# Sheet2.net
KiCad netlist of a schematic drawn in Altium Designer
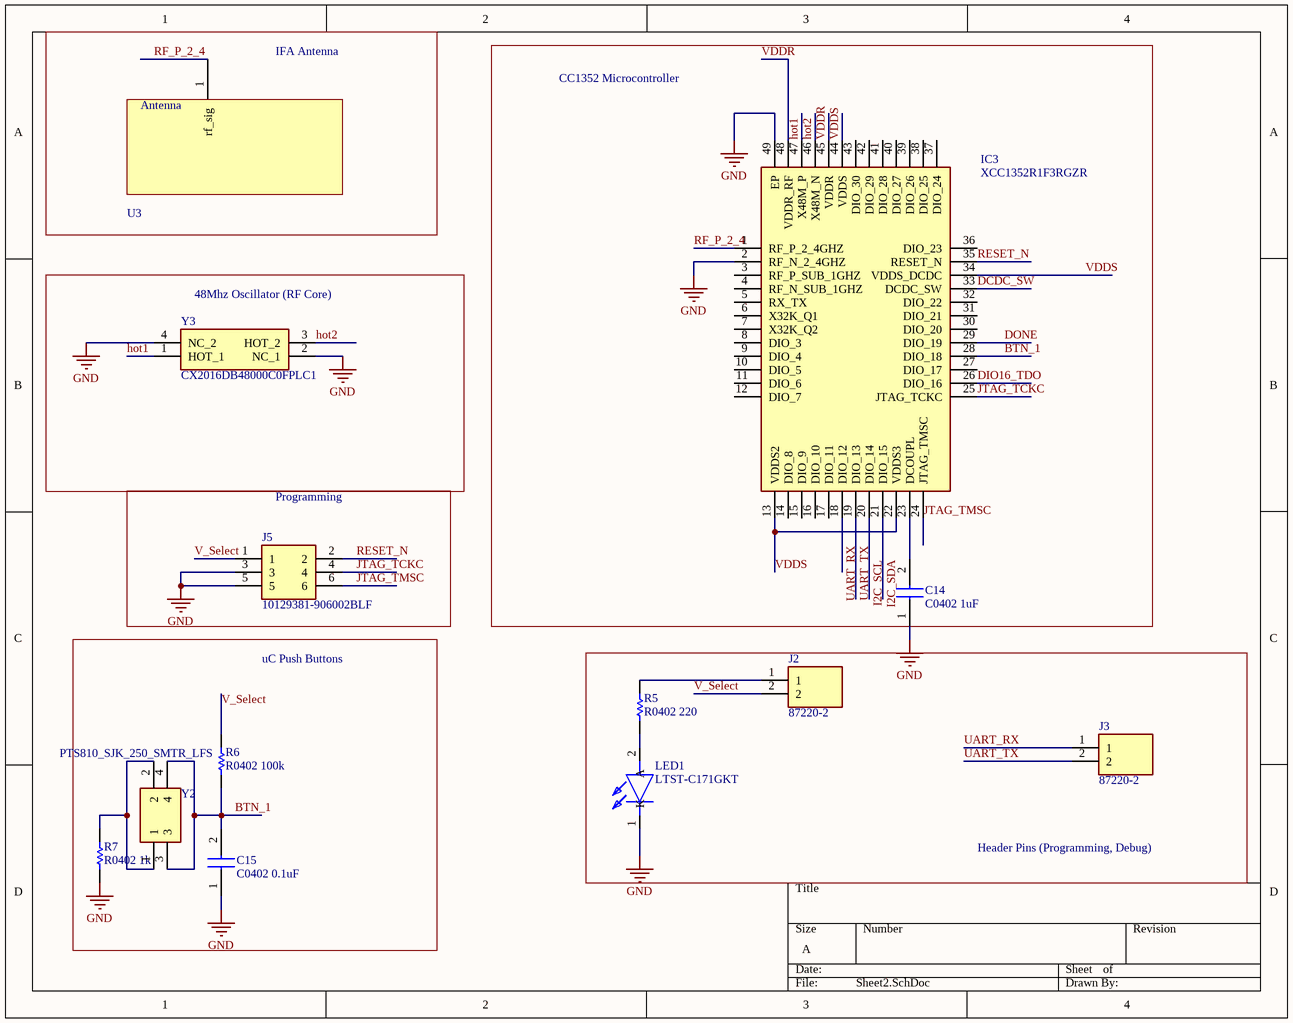
[diagram p0: Sheet2.SchDoc]

(export (version "E")
  (design (tool "Eeschema 10.0.6"))
  (components
    (comp (ref "C14")
      (value "C0402 1uF")
      (footprint "SamacSys:CAPC0603X33N")
      (description "Capacitor")
      (fields
        (field (name "MANUFACTURER_PART_NUMBER") "02014D474MAT2A")
        (field (name "MOUSER PART NUMBER") "581-02014D474MAT2A")
      )
      (libsource (lib "*") (part "02014D474MAT2A"))
    )
    (comp (ref "C15")
      (value "C0402 0.1uF")
      (footprint "SamacSys:CAPC0603X33N")
      (description "Capacitor")
      (fields
        (field (name "MANUFACTURER_PART_NUMBER") "02014D474MAT2A")
        (field (name "MOUSER PART NUMBER") "581-02014D474MAT2A")
      )
      (libsource (lib "*") (part "02014D474MAT2A"))
    )
    (comp (ref "IC3")
      (value "XCC1352R1F3RGZR")
      (footprint "SamacSys:QFN50P700X700X100-49N-D")
      (description "Integrated Circuit")
      (libsource (lib "*") (part "XCC1352R1F3RGZR"))
    )
    (comp (ref "J2")
      (value "87220-2")
      (footprint "SamacSys:HDRV2W67P0X254_1X2_467X234X1083P")
      (description "Connector")
      (fields (field (name "MOUSER PART NUMBER") "571-872202") (field (name "RS PART NUMBER") "7202418P"))
      (libsource (lib "*") (part "87220-2"))
    )
    (comp (ref "J3")
      (value "87220-2")
      (footprint "SamacSys:HDRV2W67P0X254_1X2_467X234X1083P")
      (description "Connector")
      (fields (field (name "MOUSER PART NUMBER") "571-872202") (field (name "RS PART NUMBER") "7202418P"))
      (libsource (lib "*") (part "87220-2"))
    )
    (comp (ref "J5")
      (value "10129381-906002BLF")
      (footprint "SamacSys:HDRV6W67P254_2X3_762X483X858P")
      (description "Connector")
      (fields (field (name "MOUSER PART NUMBER") "649-1012938190602BLF"))
      (libsource (lib "*") (part "10129381-906002BLF"))
    )
    (comp (ref "LED1")
      (value "LTST-C171GKT")
      (footprint "SamacSys:LEDC2012X90N")
      (description "LED")
      (fields
        (field (name "MOUSER PART NUMBER") "859-LTST-C171GKT")
        (field (name "RS PART NUMBER") "6920935P")
      )
      (libsource (lib "*") (part "LTST-C171GKT"))
    )
    (comp (ref "R5")
      (value "R0402 220")
      (footprint "RESC1005X40X25NL05T05")
      (fields (field (name "MANUFACTURER") "Vishay Dale") (field (name "PART NUMBER") "CRCW040210K0FKED"))
      (libsource (lib "Altium Content Vault") (part "RES"))
    )
    (comp (ref "R6")
      (value "R0402 100k")
      (footprint "RESC1005X40X25NL05T05")
      (fields (field (name "MANUFACTURER") "Vishay Dale") (field (name "PART NUMBER") "CRCW040210K0FKED"))
      (libsource (lib "Altium Content Vault") (part "RES"))
    )
    (comp (ref "R7")
      (value "R0402 1k")
      (footprint "RESC1005X40X25NL05T05")
      (fields (field (name "MANUFACTURER") "Vishay Dale") (field (name "PART NUMBER") "CRCW040210K0FKED"))
      (libsource (lib "Altium Content Vault") (part "RES"))
    )
    (comp (ref "U3")
      (value "RF_ANTENNA_2")
      (footprint "RF_TRACE_ANTENNA_2")
      (libsource (lib "V3_Lib") (part "RF_ANTENNA_2"))
    )
    (comp (ref "Y2")
      (value "PTS810_SJK_250_SMTR_LFS")
      (footprint "SamacSys:PTS810SJK250SMTRLFS")
      (description "Crystal or Oscillator")
      (fields
        (field (name "MANUFACTURER_PART_NUMBER") "PTS810 SJK 250 SMTR LFS")
        (field (name "MOUSER PART NUMBER") "611-PTS810SJK250SMTR")
      )
      (libsource (lib "*") (part "PTS810_SJK_250_SMTR_LFS"))
    )
    (comp (ref "Y3")
      (value "CX2016DB48000C0FPLC1")
      (footprint "SamacSys:CX2016DB48000C0FPLC1")
      (description "Crystal or Oscillator")
      (fields (field (name "MOUSER PART NUMBER") "581-CX2016DB48CFPLC1"))
      (libsource (lib "*") (part "CX2016DB48000C0FPLC1"))
    )
  )
  (nets
    (net (code "1") (name "/BTN_1") (class "Default")
      (node (ref "C15") (pin "2") (pinfunction "2_2") (pintype "passive"))
      (node (ref "IC3") (pin "28") (pinfunction "DIO_18_28") (pintype "passive"))
      (node (ref "R6") (pin "1") (pinfunction "1_1") (pintype "passive"))
      (node (ref "Y2") (pin "3") (pinfunction "3_3") (pintype "passive"))
      (node (ref "Y2") (pin "4") (pinfunction "4_4") (pintype "passive"))
    )
    (net (code "2") (name "/DCDC_SW") (class "Default")
      (node (ref "IC3") (pin "33") (pinfunction "DCDC_SW_33") (pintype "passive"))
    )
    (net (code "3") (name "/DIO16_TDO") (class "Default")
      (node (ref "IC3") (pin "26") (pinfunction "DIO_16_26") (pintype "passive"))
    )
    (net (code "4") (name "/DONE") (class "Default")
      (node (ref "IC3") (pin "29") (pinfunction "DIO_19_29") (pintype "passive"))
    )
    (net (code "5") (name "/I2C_SCL") (class "Default")
      (node (ref "IC3") (pin "20") (pinfunction "DIO_14_20") (pintype "passive"))
    )
    (net (code "6") (name "/I2C_SDA") (class "Default")
      (node (ref "IC3") (pin "21") (pinfunction "DIO_15_21") (pintype "passive"))
    )
    (net (code "7") (name "/JTAG_TCKC") (class "Default")
      (node (ref "IC3") (pin "25") (pinfunction "JTAG_TCKC_25") (pintype "passive"))
      (node (ref "J5") (pin "4") (pinfunction "4_4") (pintype "passive"))
    )
    (net (code "8") (name "/JTAG_TMSC") (class "Default")
      (node (ref "IC3") (pin "24") (pinfunction "JTAG_TMSC_24") (pintype "passive"))
      (node (ref "J5") (pin "6") (pinfunction "6_6") (pintype "passive"))
    )
    (net (code "9") (name "/RESET_N") (class "Default")
      (node (ref "IC3") (pin "35") (pinfunction "RESET_N_35") (pintype "passive"))
      (node (ref "J5") (pin "2") (pinfunction "2_2") (pintype "passive"))
    )
    (net (code "10") (name "/RF_P_2_4") (class "Default")
      (node (ref "IC3") (pin "1") (pinfunction "RF_P_2_4GHZ_1") (pintype "passive"))
      (node (ref "U3") (pin "1") (pinfunction "rf_sig_1") (pintype "passive"))
    )
    (net (code "11") (name "/UART_RX") (class "Default")
      (node (ref "IC3") (pin "18") (pinfunction "DIO_12_18") (pintype "passive"))
      (node (ref "J3") (pin "1") (pinfunction "1_1") (pintype "passive"))
    )
    (net (code "12") (name "/UART_TX") (class "Default")
      (node (ref "IC3") (pin "19") (pinfunction "DIO_13_19") (pintype "passive"))
      (node (ref "J3") (pin "2") (pinfunction "2_2") (pintype "passive"))
    )
    (net (code "13") (name "/VDDR") (class "Default")
      (node (ref "IC3") (pin "45") (pinfunction "VDDR_45") (pintype "passive"))
      (node (ref "IC3") (pin "48") (pinfunction "VDDR_RF_48") (pintype "passive"))
    )
    (net (code "14") (name "/VDDS") (class "Default")
      (node (ref "IC3") (pin "13") (pinfunction "VDDS2_13") (pintype "passive"))
      (node (ref "IC3") (pin "22") (pinfunction "VDDS3_22") (pintype "passive"))
      (node (ref "IC3") (pin "34") (pinfunction "VDDS_DCDC_34") (pintype "passive"))
      (node (ref "IC3") (pin "44") (pinfunction "VDDS_44") (pintype "passive"))
    )
    (net (code "15") (name "/V_Select") (class "Default")
      (node (ref "J2") (pin "2") (pinfunction "2_2") (pintype "passive"))
      (node (ref "J5") (pin "1") (pinfunction "1_1") (pintype "passive"))
      (node (ref "R6") (pin "2") (pinfunction "2_2") (pintype "passive"))
    )
    (net (code "16") (name "/hot1") (class "Default")
      (node (ref "IC3") (pin "47") (pinfunction "X48M_P_47") (pintype "passive"))
      (node (ref "Y3") (pin "1") (pinfunction "HOT_1_1") (pintype "passive"))
    )
    (net (code "17") (name "/hot2") (class "Default")
      (node (ref "IC3") (pin "46") (pinfunction "X48M_N_46") (pintype "passive"))
      (node (ref "Y3") (pin "3") (pinfunction "HOT_2_3") (pintype "passive"))
    )
    (net (code "18") (name "GND") (class "Default")
      (node (ref "C14") (pin "1") (pinfunction "1_1") (pintype "passive"))
      (node (ref "C15") (pin "1") (pinfunction "1_1") (pintype "passive"))
      (node (ref "IC3") (pin "2") (pinfunction "RF_N_2_4GHZ_2") (pintype "passive"))
      (node (ref "IC3") (pin "49") (pinfunction "EP_49") (pintype "passive"))
      (node (ref "J5") (pin "3") (pinfunction "3_3") (pintype "passive"))
      (node (ref "J5") (pin "5") (pinfunction "5_5") (pintype "passive"))
      (node (ref "LED1") (pin "1") (pinfunction "K_1") (pintype "passive"))
      (node (ref "R7") (pin "1") (pinfunction "1_1") (pintype "passive"))
      (node (ref "Y3") (pin "2") (pinfunction "NC_1_2") (pintype "passive"))
      (node (ref "Y3") (pin "4") (pinfunction "NC_2_4") (pintype "passive"))
    )
    (net (code "19") (name "Net-(IC3-DCOUPL)") (class "Default")
      (node (ref "C14") (pin "2") (pinfunction "2_2") (pintype "passive"))
      (node (ref "IC3") (pin "23") (pinfunction "DCOUPL_23") (pintype "passive"))
    )
    (net (code "20") (name "Net-(J2-Pad1)") (class "Default")
      (node (ref "J2") (pin "1") (pinfunction "1_1") (pintype "passive"))
      (node (ref "R5") (pin "2") (pinfunction "2_2") (pintype "passive"))
    )
    (net (code "21") (name "Net-(LED1-A)") (class "Default")
      (node (ref "LED1") (pin "2") (pinfunction "A_2") (pintype "passive"))
      (node (ref "R5") (pin "1") (pinfunction "1_1") (pintype "passive"))
    )
    (net (code "22") (name "Net-(R7-Pad2)") (class "Default")
      (node (ref "R7") (pin "2") (pinfunction "2_2") (pintype "passive"))
      (node (ref "Y2") (pin "1") (pinfunction "1_1") (pintype "passive"))
      (node (ref "Y2") (pin "2") (pinfunction "2_2") (pintype "passive"))
    )
    (net (code "23") (name "unconnected-(IC3-DIO_3-Pad8)") (class "Default")
      (node (ref "IC3") (pin "8") (pinfunction "DIO_3_8") (pintype "passive"))
    )
    (net (code "24") (name "unconnected-(IC3-DIO_4-Pad9)") (class "Default")
      (node (ref "IC3") (pin "9") (pinfunction "DIO_4_9") (pintype "passive"))
    )
    (net (code "25") (name "unconnected-(IC3-DIO_5-Pad10)") (class "Default")
      (node (ref "IC3") (pin "10") (pinfunction "DIO_5_10") (pintype "passive"))
    )
    (net (code "26") (name "unconnected-(IC3-DIO_6-Pad11)") (class "Default")
      (node (ref "IC3") (pin "11") (pinfunction "DIO_6_11") (pintype "passive"))
    )
    (net (code "27") (name "unconnected-(IC3-DIO_7-Pad12)") (class "Default")
      (node (ref "IC3") (pin "12") (pinfunction "DIO_7_12") (pintype "passive"))
    )
    (net (code "28") (name "unconnected-(IC3-DIO_8-Pad14)") (class "Default")
      (node (ref "IC3") (pin "14") (pinfunction "DIO_8_14") (pintype "passive"))
    )
    (net (code "29") (name "unconnected-(IC3-DIO_9-Pad15)") (class "Default")
      (node (ref "IC3") (pin "15") (pinfunction "DIO_9_15") (pintype "passive"))
    )
    (net (code "30") (name "unconnected-(IC3-DIO_10-Pad16)") (class "Default")
      (node (ref "IC3") (pin "16") (pinfunction "DIO_10_16") (pintype "passive"))
    )
    (net (code "31") (name "unconnected-(IC3-DIO_11-Pad17)") (class "Default")
      (node (ref "IC3") (pin "17") (pinfunction "DIO_11_17") (pintype "passive"))
    )
    (net (code "32") (name "unconnected-(IC3-DIO_17-Pad27)") (class "Default")
      (node (ref "IC3") (pin "27") (pinfunction "DIO_17_27") (pintype "passive"))
    )
    (net (code "33") (name "unconnected-(IC3-DIO_20-Pad30)") (class "Default")
      (node (ref "IC3") (pin "30") (pinfunction "DIO_20_30") (pintype "passive"))
    )
    (net (code "34") (name "unconnected-(IC3-DIO_21-Pad31)") (class "Default")
      (node (ref "IC3") (pin "31") (pinfunction "DIO_21_31") (pintype "passive"))
    )
    (net (code "35") (name "unconnected-(IC3-DIO_22-Pad32)") (class "Default")
      (node (ref "IC3") (pin "32") (pinfunction "DIO_22_32") (pintype "passive"))
    )
    (net (code "36") (name "unconnected-(IC3-DIO_23-Pad36)") (class "Default")
      (node (ref "IC3") (pin "36") (pinfunction "DIO_23_36") (pintype "passive"))
    )
    (net (code "37") (name "unconnected-(IC3-DIO_24-Pad37)") (class "Default")
      (node (ref "IC3") (pin "37") (pinfunction "DIO_24_37") (pintype "passive"))
    )
    (net (code "38") (name "unconnected-(IC3-DIO_25-Pad38)") (class "Default")
      (node (ref "IC3") (pin "38") (pinfunction "DIO_25_38") (pintype "passive"))
    )
    (net (code "39") (name "unconnected-(IC3-DIO_26-Pad39)") (class "Default")
      (node (ref "IC3") (pin "39") (pinfunction "DIO_26_39") (pintype "passive"))
    )
    (net (code "40") (name "unconnected-(IC3-DIO_27-Pad40)") (class "Default")
      (node (ref "IC3") (pin "40") (pinfunction "DIO_27_40") (pintype "passive"))
    )
    (net (code "41") (name "unconnected-(IC3-DIO_28-Pad41)") (class "Default")
      (node (ref "IC3") (pin "41") (pinfunction "DIO_28_41") (pintype "passive"))
    )
    (net (code "42") (name "unconnected-(IC3-DIO_29-Pad42)") (class "Default")
      (node (ref "IC3") (pin "42") (pinfunction "DIO_29_42") (pintype "passive"))
    )
    (net (code "43") (name "unconnected-(IC3-DIO_30-Pad43)") (class "Default")
      (node (ref "IC3") (pin "43") (pinfunction "DIO_30_43") (pintype "passive"))
    )
    (net (code "44") (name "unconnected-(IC3-RF_N_SUB_1GHZ-Pad4)") (class "Default")
      (node (ref "IC3") (pin "4") (pinfunction "RF_N_SUB_1GHZ_4") (pintype "passive"))
    )
    (net (code "45") (name "unconnected-(IC3-RF_P_SUB_1GHZ-Pad3)") (class "Default")
      (node (ref "IC3") (pin "3") (pinfunction "RF_P_SUB_1GHZ_3") (pintype "passive"))
    )
    (net (code "46") (name "unconnected-(IC3-RX_TX-Pad5)") (class "Default")
      (node (ref "IC3") (pin "5") (pinfunction "RX_TX_5") (pintype "passive"))
    )
    (net (code "47") (name "unconnected-(IC3-X32K_Q1-Pad6)") (class "Default")
      (node (ref "IC3") (pin "6") (pinfunction "X32K_Q1_6") (pintype "passive"))
    )
    (net (code "48") (name "unconnected-(IC3-X32K_Q2-Pad7)") (class "Default")
      (node (ref "IC3") (pin "7") (pinfunction "X32K_Q2_7") (pintype "passive"))
    )
  )
)
